# Sensor_AFE_Explorer_Rev1.net
KiCad netlist of a schematic drawn in EAGLE
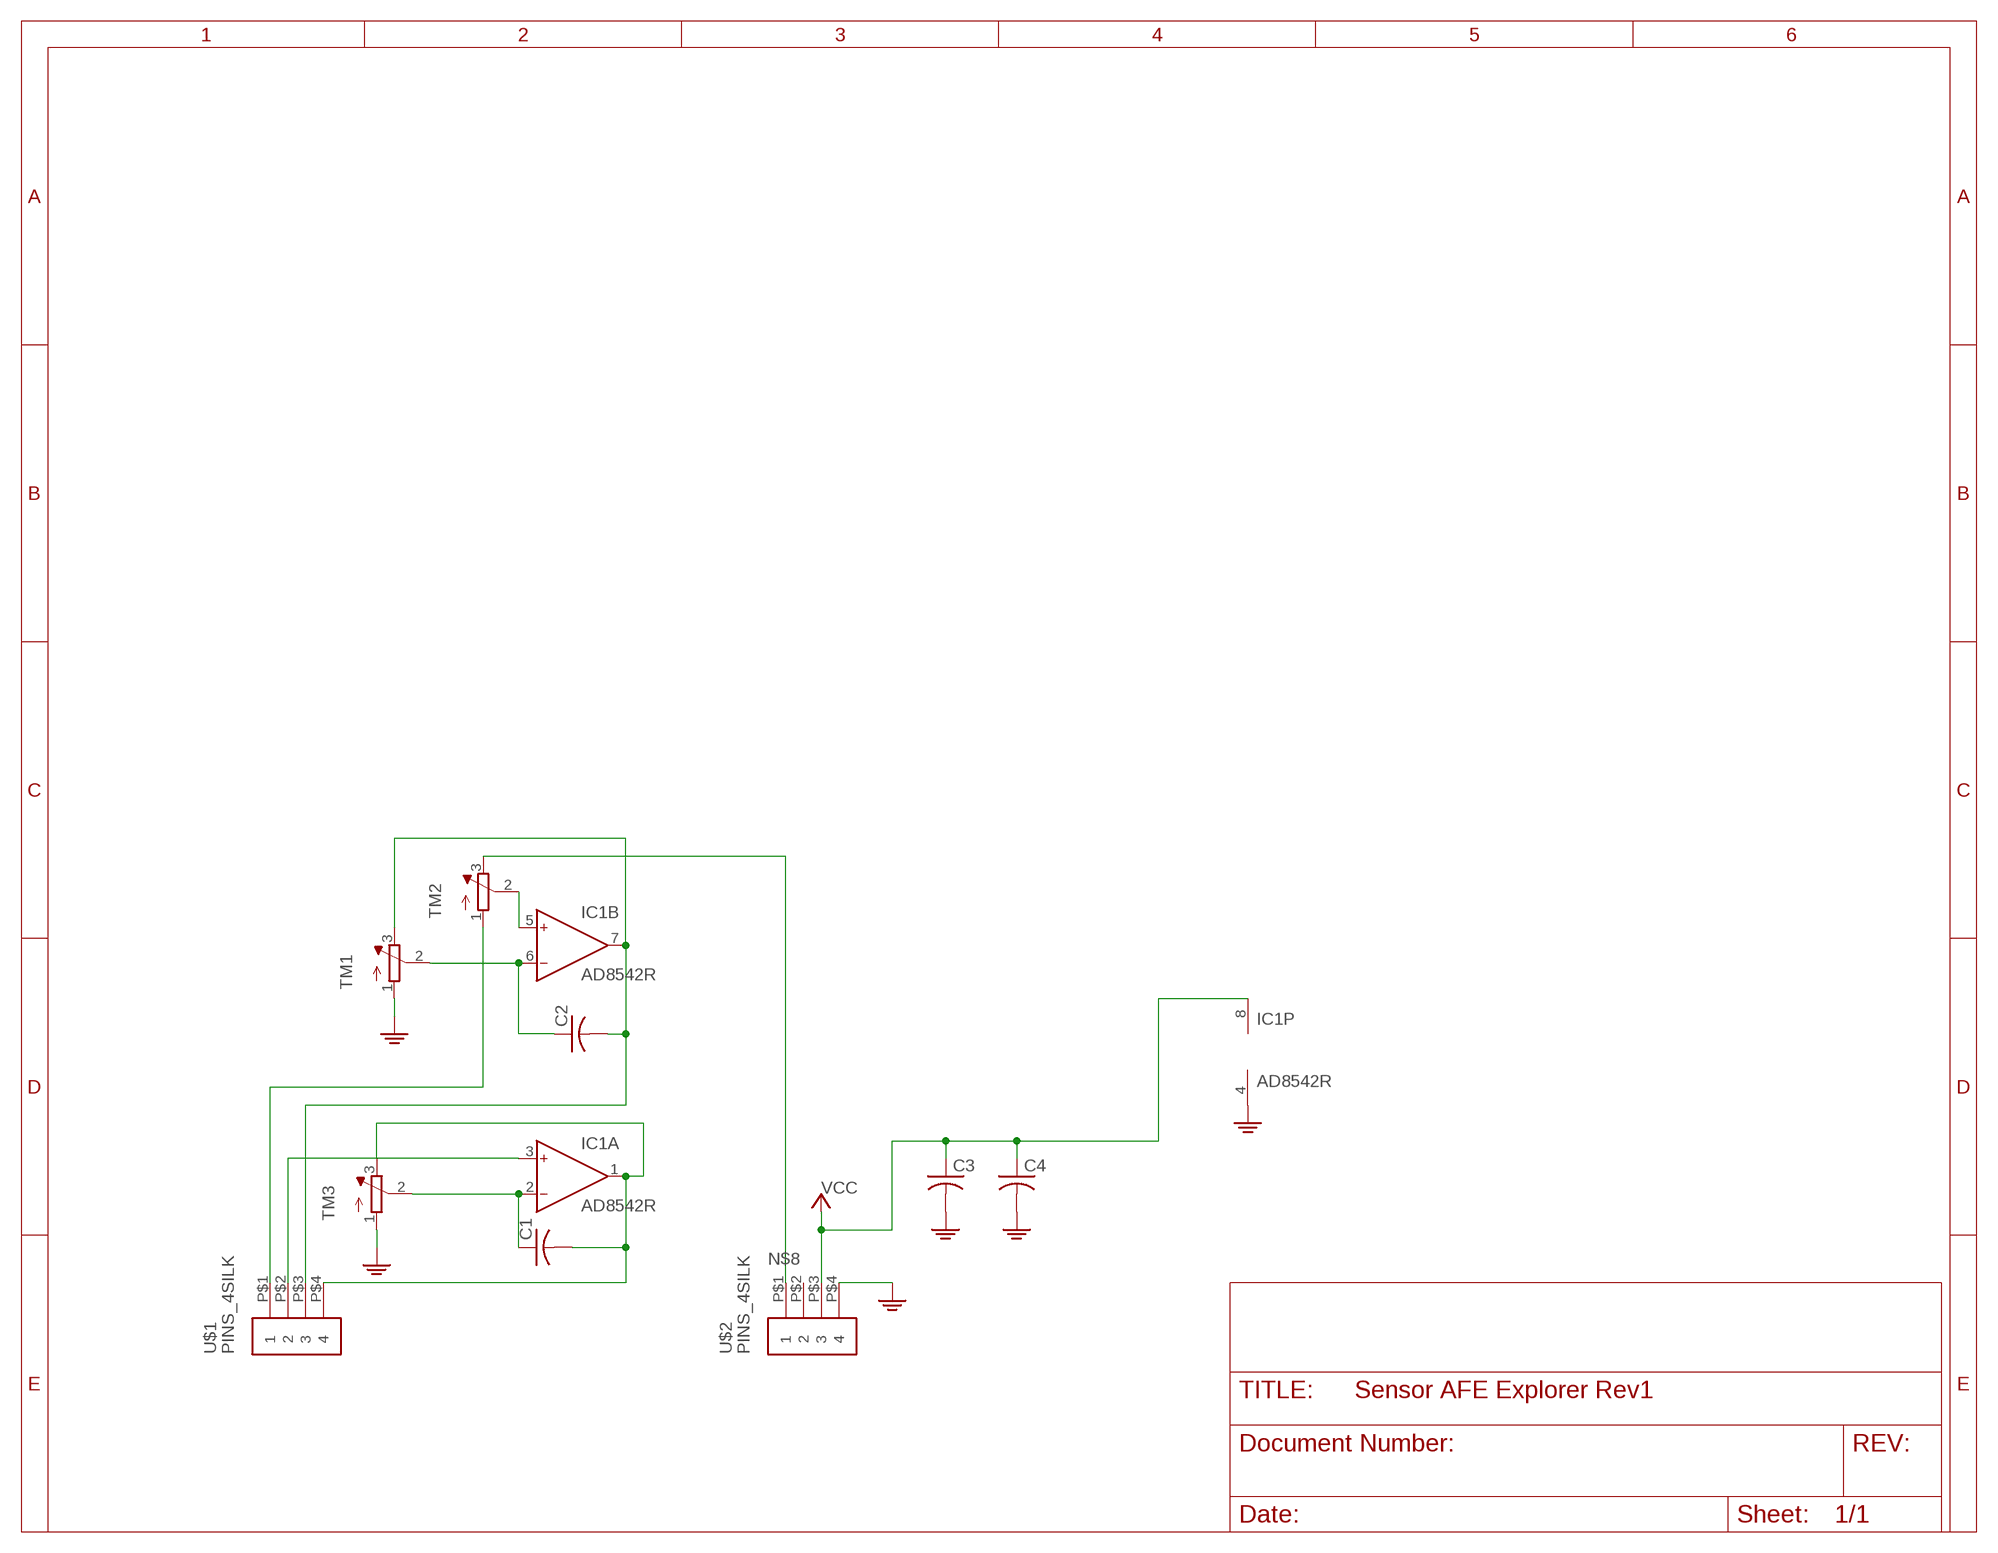
[diagram p0: schematic, sheet 1]

(export (version "E")
  (design (tool "Eeschema 10.0.6"))
  (components
    (comp (ref "C1")
      (value "C-USC0805")
      (footprint "eagle-import:C0805")
      (libsource (lib "eagle-import") (part "C-USC0805"))
    )
    (comp (ref "C2")
      (value "C-USC0805")
      (footprint "eagle-import:C0805")
      (libsource (lib "eagle-import") (part "C-USC0805"))
    )
    (comp (ref "C3")
      (value "C-USC0805")
      (footprint "eagle-import:C0805")
      (libsource (lib "eagle-import") (part "C-USC0805"))
    )
    (comp (ref "C4")
      (value "C-USC0805")
      (footprint "eagle-import:C0805")
      (libsource (lib "eagle-import") (part "C-USC0805"))
    )
    (comp (ref "IC1")
      (value "AD8542R")
      (footprint "eagle-import:SO8")
      (fields (field (name "MF") "ALTERA CORPORATION") (field (name "MPN") "AD8542ARZ-REEL"))
      (libsource (lib "eagle-import") (part "AD8542R"))
    )
    (comp (ref "TM1")
      (value "TRIMPOT3386")
      (footprint "eagle-import:TRIM-3386")
      (libsource (lib "eagle-import") (part "TRIMPOT3386"))
    )
    (comp (ref "TM2")
      (value "TRIMPOT3386")
      (footprint "eagle-import:TRIM-3386")
      (libsource (lib "eagle-import") (part "TRIMPOT3386"))
    )
    (comp (ref "TM3")
      (value "TRIMPOT3386")
      (footprint "eagle-import:TRIM-3386")
      (libsource (lib "eagle-import") (part "TRIMPOT3386"))
    )
    (comp (ref "U$1")
      (value "PINS_4SILK")
      (footprint "eagle-import:PCB_4")
      (libsource (lib "eagle-import") (part "PINS_4SILK"))
    )
    (comp (ref "U$2")
      (value "PINS_4SILK")
      (footprint "eagle-import:PCB_4")
      (libsource (lib "eagle-import") (part "PINS_4SILK"))
    )
  )
  (nets
    (net (code "1") (name "/N$8") (class "Default")
      (node (ref "TM2") (pin "3") (pinfunction "E_3") (pintype "passive"))
      (node (ref "U$2") (pin "P$1") (pinfunction "1_P$1") (pintype "bidirectional"))
    )
    (net (code "2") (name "GND") (class "Default")
      (node (ref "C3") (pin "2") (pinfunction "2_2") (pintype "passive"))
      (node (ref "C4") (pin "2") (pinfunction "2_2") (pintype "passive"))
      (node (ref "IC1") (pin "4") (pinfunction "V-_4") (pintype "power_in"))
      (node (ref "TM1") (pin "1") (pinfunction "A_1") (pintype "passive"))
      (node (ref "TM3") (pin "1") (pinfunction "A_1") (pintype "passive"))
      (node (ref "U$2") (pin "P$4") (pinfunction "4_P$4") (pintype "bidirectional"))
    )
    (net (code "3") (name "Net-(IC1A-IN+)") (class "Default")
      (node (ref "IC1") (pin "3") (pinfunction "IN+_3") (pintype "input"))
      (node (ref "U$1") (pin "P$2") (pinfunction "2_P$2") (pintype "bidirectional"))
    )
    (net (code "4") (name "Net-(IC1A-IN-)") (class "Default")
      (node (ref "C1") (pin "1") (pinfunction "1_1") (pintype "passive"))
      (node (ref "IC1") (pin "2") (pinfunction "IN-_2") (pintype "input"))
      (node (ref "TM3") (pin "2") (pinfunction "S_2") (pintype "passive"))
    )
    (net (code "5") (name "Net-(IC1A-OUT)") (class "Default")
      (node (ref "C1") (pin "2") (pinfunction "2_2") (pintype "passive"))
      (node (ref "IC1") (pin "1") (pinfunction "OUT_1") (pintype "output"))
      (node (ref "TM3") (pin "3") (pinfunction "E_3") (pintype "passive"))
      (node (ref "U$1") (pin "P$4") (pinfunction "4_P$4") (pintype "bidirectional"))
    )
    (net (code "6") (name "Net-(IC1B-IN+)") (class "Default")
      (node (ref "IC1") (pin "5") (pinfunction "IN+_5") (pintype "input"))
      (node (ref "TM2") (pin "2") (pinfunction "S_2") (pintype "passive"))
    )
    (net (code "7") (name "Net-(IC1B-IN-)") (class "Default")
      (node (ref "C2") (pin "1") (pinfunction "1_1") (pintype "passive"))
      (node (ref "IC1") (pin "6") (pinfunction "IN-_6") (pintype "input"))
      (node (ref "TM1") (pin "2") (pinfunction "S_2") (pintype "passive"))
    )
    (net (code "8") (name "Net-(IC1B-OUT)") (class "Default")
      (node (ref "C2") (pin "2") (pinfunction "2_2") (pintype "passive"))
      (node (ref "IC1") (pin "7") (pinfunction "OUT_7") (pintype "output"))
      (node (ref "TM1") (pin "3") (pinfunction "E_3") (pintype "passive"))
      (node (ref "U$1") (pin "P$3") (pinfunction "3_P$3") (pintype "bidirectional"))
    )
    (net (code "9") (name "Net-(TM2-A)") (class "Default")
      (node (ref "TM2") (pin "1") (pinfunction "A_1") (pintype "passive"))
      (node (ref "U$1") (pin "P$1") (pinfunction "1_P$1") (pintype "bidirectional"))
    )
    (net (code "10") (name "VCC") (class "Default")
      (node (ref "C3") (pin "1") (pinfunction "1_1") (pintype "passive"))
      (node (ref "C4") (pin "1") (pinfunction "1_1") (pintype "passive"))
      (node (ref "IC1") (pin "8") (pinfunction "V+_8") (pintype "power_in"))
      (node (ref "U$2") (pin "P$3") (pinfunction "3_P$3") (pintype "bidirectional"))
    )
    (net (code "11") (name "unconnected-(U$2-2-PadP$2)") (class "Default")
      (node (ref "U$2") (pin "P$2") (pinfunction "2_P$2") (pintype "bidirectional"))
    )
  )
)
